# CW340_USBHUB_ExtPorts.net
KiCad netlist of a schematic drawn in Altium Designer
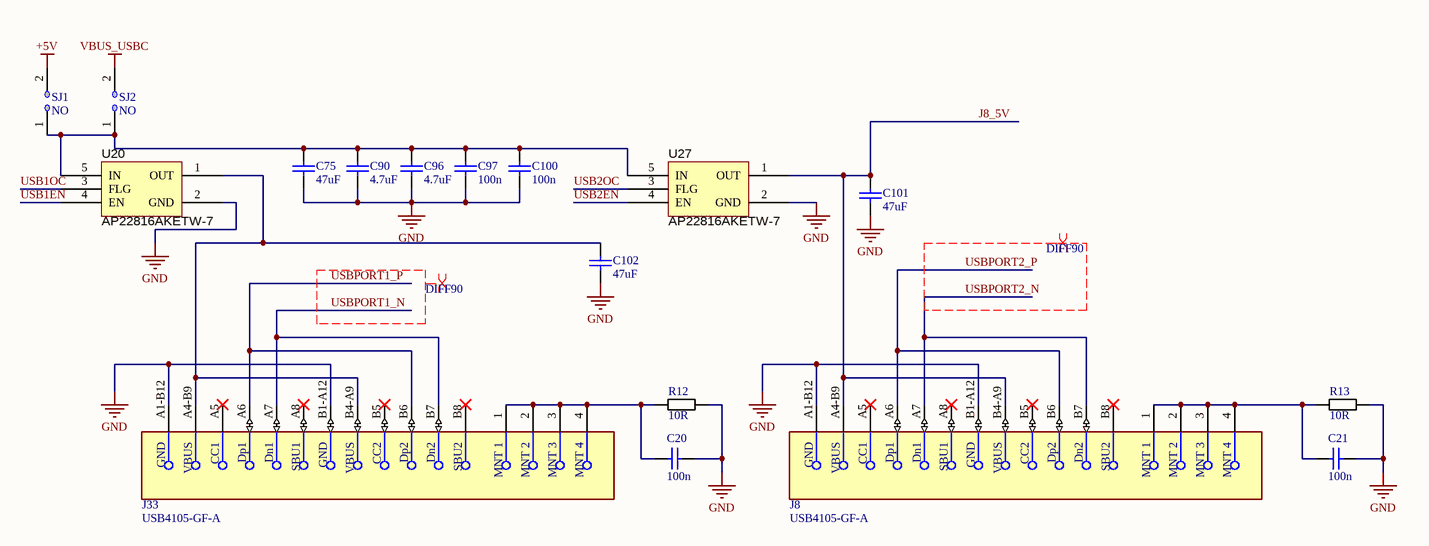
[diagram p0: CW340_USBHUB_ExtPorts.SchDoc]

(export (version "E")
  (design (tool "Eeschema 10.0.6"))
  (components
    (comp (ref "C20")
      (value "100n")
      (footprint "CAPC0603_M")
      (description "100n, 0603")
      (fields (field (name "PART NUMBER") "CCHIP-100n-0603"))
      (libsource (lib "NewAE_AltiumLib") (part "CAP"))
    )
    (comp (ref "C21")
      (value "100n")
      (footprint "CAPC0603_M")
      (description "100n, 0603")
      (fields (field (name "PART NUMBER") "CCHIP-100n-0603"))
      (libsource (lib "NewAE_AltiumLib") (part "CAP"))
    )
    (comp (ref "C75")
      (value "47uF")
      (footprint "CAPC3225X20N")
      (description "47u, 10V, 1210, Ceramic")
      (fields (field (name "PART NUMBER") "CCHIP-47u-1210") (field (name "TOLERANCE") "20%"))
      (libsource (lib "NewAE_AltiumLib") (part "CAP"))
    )
    (comp (ref "C90")
      (value "4.7uF")
      (footprint "CAPC0805_M")
      (description "4u7, 35V, 0805, Ceramic")
      (fields (field (name "PART NUMBER") "CCHIP-4u7-0805-35V") (field (name "TOLERANCE") "10%"))
      (libsource (lib "NewAE_AltiumLib") (part "CAP"))
    )
    (comp (ref "C96")
      (value "4.7uF")
      (footprint "CAPC0805_M")
      (description "4u7, 35V, 0805, Ceramic")
      (fields (field (name "PART NUMBER") "CCHIP-4u7-0805-35V") (field (name "TOLERANCE") "10%"))
      (libsource (lib "NewAE_AltiumLib") (part "CAP"))
    )
    (comp (ref "C97")
      (value "100n")
      (footprint "CAPC0402_M")
      (description "100n, 0402")
      (fields (field (name "PART NUMBER") "CCHIP-100n-0402"))
      (libsource (lib "NewAE_AltiumLib") (part "CAP"))
    )
    (comp (ref "C100")
      (value "100n")
      (footprint "CAPC0402_M")
      (description "100n, 0402")
      (fields (field (name "PART NUMBER") "CCHIP-100n-0402"))
      (libsource (lib "NewAE_AltiumLib") (part "CAP"))
    )
    (comp (ref "C101")
      (value "47uF")
      (footprint "CAPC3225X20N")
      (description "47u, 10V, 1210, Ceramic")
      (fields (field (name "PART NUMBER") "CCHIP-47u-1210") (field (name "TOLERANCE") "20%"))
      (libsource (lib "NewAE_AltiumLib") (part "CAP"))
    )
    (comp (ref "C102")
      (value "47uF")
      (footprint "CAPC3225X20N")
      (description "47u, 10V, 1210, Ceramic")
      (fields (field (name "PART NUMBER") "CCHIP-47u-1210") (field (name "TOLERANCE") "20%"))
      (libsource (lib "NewAE_AltiumLib") (part "CAP"))
    )
    (comp (ref "J8")
      (value "USB4105-GF-A")
      (footprint "FP-USB4105-GF-A-MFG")
      (description "CONN RCPT USB2.0 TYPEC 5A")
      (fields
        (field (name "MANUFACTURER") "GCT")
        (field (name "OCTOPART") "https://octopart.com/usb4105-gf-a-gct-106627878")
      )
      (libsource (lib "Altium Content Vault") (part "e7c17a616881a82b79941196b4bec10"))
    )
    (comp (ref "J33")
      (value "USB4105-GF-A")
      (footprint "FP-USB4105-GF-A-MFG")
      (description "CONN RCPT USB2.0 TYPEC 5A")
      (fields
        (field (name "MANUFACTURER") "GCT")
        (field (name "OCTOPART") "https://octopart.com/usb4105-gf-a-gct-106627878")
      )
      (libsource (lib "Altium Content Vault") (part "e7c17a616881a82b79941196b4bec10"))
    )
    (comp (ref "R12")
      (value "10R")
      (footprint "RESC1608X55N")
      (description "10R res, 0603, 1%, 1/10W")
      (fields (field (name "PART NUMBER") "RCHIP-10R-0603") (field (name "TOLERANCE") "1%"))
      (libsource (lib "NewAE_AltiumLib") (part "RES-EU"))
    )
    (comp (ref "R13")
      (value "10R")
      (footprint "RESC1608X55N")
      (description "10R res, 0603, 1%, 1/10W")
      (fields (field (name "PART NUMBER") "RCHIP-10R-0603") (field (name "TOLERANCE") "1%"))
      (libsource (lib "NewAE_AltiumLib") (part "RES-EU"))
    )
    (comp (ref "SJ1")
      (value "NO")
      (footprint "SJ_2S_NO")
      (description "Solder Jumper, NO")
      (fields (field (name "PART NUMBER") "SJ_2S_NO"))
      (libsource (lib "NewAE_AltiumLib") (part "SJ_2S_NO"))
    )
    (comp (ref "SJ2")
      (value "NO")
      (footprint "SJ_2S_NO")
      (description "Solder Jumper, NO")
      (fields (field (name "PART NUMBER") "SJ_2S_NO"))
      (libsource (lib "NewAE_AltiumLib") (part "SJ_2S_NO"))
    )
    (comp (ref "U20")
      (value "AP22816AKETW-7")
      (footprint "SOT23-5P95_285X145L45X40")
      (description "USB Power Switch, Digital IC")
      (fields (field (name "PART NUMBER") "AP22816AKE") (field (name "CREATED BY") "D.GODDARD"))
      (libsource (lib "NewAE_AltiumLib") (part "AP22802"))
    )
    (comp (ref "U27")
      (value "AP22816AKETW-7")
      (footprint "SOT23-5P95_285X145L45X40")
      (description "USB Power Switch, Digital IC")
      (fields (field (name "PART NUMBER") "AP22816AKE") (field (name "CREATED BY") "D.GODDARD"))
      (libsource (lib "NewAE_AltiumLib") (part "AP22802"))
    )
  )
  (nets
    (net (code "1") (name "+5V") (class "Default")
      (node (ref "SJ1") (pin "2") (pinfunction "2_2") (pintype "passive"))
    )
    (net (code "2") (name "/J8_5V") (class "Default")
      (node (ref "C101") (pin "1") (pinfunction "1_1") (pintype "passive"))
      (node (ref "J8") (pin "A4-B9") (pinfunction "VBUS_A4-B9") (pintype "power_in"))
      (node (ref "J8") (pin "B4-A9") (pinfunction "VBUS_B4-A9") (pintype "bidirectional"))
      (node (ref "U27") (pin "1") (pinfunction "OUT_1") (pintype "passive"))
    )
    (net (code "3") (name "/USB1EN") (class "Default")
      (node (ref "U20") (pin "4") (pinfunction "EN_4") (pintype "passive"))
    )
    (net (code "4") (name "/USB1OC") (class "Default")
      (node (ref "U20") (pin "3") (pinfunction "FLG_3") (pintype "passive"))
    )
    (net (code "5") (name "/USB2EN") (class "Default")
      (node (ref "U27") (pin "4") (pinfunction "EN_4") (pintype "passive"))
    )
    (net (code "6") (name "/USB2OC") (class "Default")
      (node (ref "U27") (pin "3") (pinfunction "FLG_3") (pintype "passive"))
    )
    (net (code "7") (name "/USBPORT1_N") (class "Default")
      (node (ref "J33") (pin "A7") (pinfunction "Dn1_A7") (pintype "bidirectional"))
      (node (ref "J33") (pin "B7") (pinfunction "Dn2_B7") (pintype "bidirectional"))
    )
    (net (code "8") (name "/USBPORT1_P") (class "Default")
      (node (ref "J33") (pin "A6") (pinfunction "Dp1_A6") (pintype "bidirectional"))
      (node (ref "J33") (pin "B6") (pinfunction "Dp2_B6") (pintype "bidirectional"))
    )
    (net (code "9") (name "/USBPORT2_N") (class "Default")
      (node (ref "J8") (pin "A7") (pinfunction "Dn1_A7") (pintype "bidirectional"))
      (node (ref "J8") (pin "B7") (pinfunction "Dn2_B7") (pintype "bidirectional"))
    )
    (net (code "10") (name "/USBPORT2_P") (class "Default")
      (node (ref "J8") (pin "A6") (pinfunction "Dp1_A6") (pintype "bidirectional"))
      (node (ref "J8") (pin "B6") (pinfunction "Dp2_B6") (pintype "bidirectional"))
    )
    (net (code "11") (name "GND") (class "Default")
      (node (ref "C100") (pin "2") (pinfunction "2_2") (pintype "passive"))
      (node (ref "C101") (pin "2") (pinfunction "2_2") (pintype "passive"))
      (node (ref "C102") (pin "2") (pinfunction "2_2") (pintype "passive"))
      (node (ref "C20") (pin "2") (pinfunction "2_2") (pintype "passive"))
      (node (ref "C21") (pin "2") (pinfunction "2_2") (pintype "passive"))
      (node (ref "C75") (pin "2") (pinfunction "2_2") (pintype "passive"))
      (node (ref "C90") (pin "2") (pinfunction "2_2") (pintype "passive"))
      (node (ref "C96") (pin "2") (pinfunction "2_2") (pintype "passive"))
      (node (ref "C97") (pin "2") (pinfunction "2_2") (pintype "passive"))
      (node (ref "J33") (pin "A1-B12") (pinfunction "GND_A1-B12") (pintype "power_in"))
      (node (ref "J33") (pin "B1-A12") (pinfunction "GND_B1-A12") (pintype "bidirectional"))
      (node (ref "J8") (pin "A1-B12") (pinfunction "GND_A1-B12") (pintype "power_in"))
      (node (ref "J8") (pin "B1-A12") (pinfunction "GND_B1-A12") (pintype "bidirectional"))
      (node (ref "R12") (pin "2") (pinfunction "2_2") (pintype "passive"))
      (node (ref "R13") (pin "2") (pinfunction "2_2") (pintype "passive"))
      (node (ref "U20") (pin "2") (pinfunction "GND_2") (pintype "passive"))
      (node (ref "U27") (pin "2") (pinfunction "GND_2") (pintype "passive"))
    )
    (net (code "12") (name "Net-(J8-MNT_1)") (class "Default")
      (node (ref "C21") (pin "1") (pinfunction "1_1") (pintype "passive"))
      (node (ref "J8") (pin "1") (pinfunction "MNT_1_1") (pintype "power_in"))
      (node (ref "J8") (pin "2") (pinfunction "MNT_2_2") (pintype "power_in"))
      (node (ref "J8") (pin "3") (pinfunction "MNT_3_3") (pintype "power_in"))
      (node (ref "J8") (pin "4") (pinfunction "MNT_4_4") (pintype "power_in"))
      (node (ref "R13") (pin "1") (pinfunction "1_1") (pintype "passive"))
    )
    (net (code "13") (name "Net-(J33-MNT_1)") (class "Default")
      (node (ref "C20") (pin "1") (pinfunction "1_1") (pintype "passive"))
      (node (ref "J33") (pin "1") (pinfunction "MNT_1_1") (pintype "power_in"))
      (node (ref "J33") (pin "2") (pinfunction "MNT_2_2") (pintype "power_in"))
      (node (ref "J33") (pin "3") (pinfunction "MNT_3_3") (pintype "power_in"))
      (node (ref "J33") (pin "4") (pinfunction "MNT_4_4") (pintype "power_in"))
      (node (ref "R12") (pin "1") (pinfunction "1_1") (pintype "passive"))
    )
    (net (code "14") (name "Net-(U20-IN)") (class "Default")
      (node (ref "C100") (pin "1") (pinfunction "1_1") (pintype "passive"))
      (node (ref "C75") (pin "1") (pinfunction "1_1") (pintype "passive"))
      (node (ref "C90") (pin "1") (pinfunction "1_1") (pintype "passive"))
      (node (ref "C96") (pin "1") (pinfunction "1_1") (pintype "passive"))
      (node (ref "C97") (pin "1") (pinfunction "1_1") (pintype "passive"))
      (node (ref "SJ1") (pin "1") (pinfunction "1_1") (pintype "passive"))
      (node (ref "SJ2") (pin "1") (pinfunction "1_1") (pintype "passive"))
      (node (ref "U20") (pin "5") (pinfunction "IN_5") (pintype "passive"))
      (node (ref "U27") (pin "5") (pinfunction "IN_5") (pintype "passive"))
    )
    (net (code "15") (name "Net-(U20-OUT)") (class "Default")
      (node (ref "C102") (pin "1") (pinfunction "1_1") (pintype "passive"))
      (node (ref "J33") (pin "A4-B9") (pinfunction "VBUS_A4-B9") (pintype "power_in"))
      (node (ref "J33") (pin "B4-A9") (pinfunction "VBUS_B4-A9") (pintype "bidirectional"))
      (node (ref "U20") (pin "1") (pinfunction "OUT_1") (pintype "passive"))
    )
    (net (code "16") (name "VBUS_USBC") (class "Default")
      (node (ref "SJ2") (pin "2") (pinfunction "2_2") (pintype "passive"))
    )
    (net (code "17") (name "unconnected-(J8-CC1-PadA5)") (class "Default")
      (node (ref "J8") (pin "A5") (pinfunction "CC1_A5") (pintype "power_in+no_connect"))
    )
    (net (code "18") (name "unconnected-(J8-CC2-PadB5)") (class "Default")
      (node (ref "J8") (pin "B5") (pinfunction "CC2_B5") (pintype "bidirectional+no_connect"))
    )
    (net (code "19") (name "unconnected-(J8-SBU1-PadA8)") (class "Default")
      (node (ref "J8") (pin "A8") (pinfunction "SBU1_A8") (pintype "bidirectional+no_connect"))
    )
    (net (code "20") (name "unconnected-(J8-SBU2-PadB8)") (class "Default")
      (node (ref "J8") (pin "B8") (pinfunction "SBU2_B8") (pintype "power_in+no_connect"))
    )
    (net (code "21") (name "unconnected-(J33-CC1-PadA5)") (class "Default")
      (node (ref "J33") (pin "A5") (pinfunction "CC1_A5") (pintype "power_in+no_connect"))
    )
    (net (code "22") (name "unconnected-(J33-CC2-PadB5)") (class "Default")
      (node (ref "J33") (pin "B5") (pinfunction "CC2_B5") (pintype "bidirectional+no_connect"))
    )
    (net (code "23") (name "unconnected-(J33-SBU1-PadA8)") (class "Default")
      (node (ref "J33") (pin "A8") (pinfunction "SBU1_A8") (pintype "bidirectional+no_connect"))
    )
    (net (code "24") (name "unconnected-(J33-SBU2-PadB8)") (class "Default")
      (node (ref "J33") (pin "B8") (pinfunction "SBU2_B8") (pintype "power_in+no_connect"))
    )
  )
)
